# led.net
KiCad netlist of a schematic drawn in EAGLE
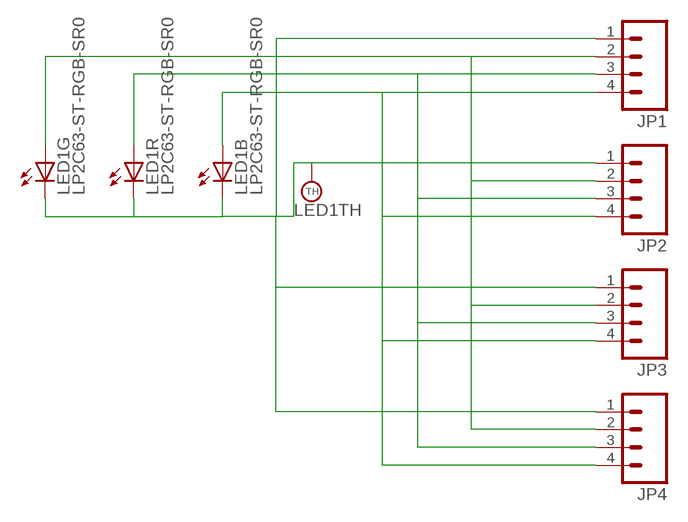
[diagram p0: schematic, sheet 1]

(export (version "E")
  (design (tool "Eeschema 10.0.6"))
  (components
    (comp (ref "JP1")
      (value "M04LONGPADS")
      (footprint "eagle-import:1X04_LONGPADS")
      (libsource (lib "eagle-import") (part "M04LONGPADS"))
    )
    (comp (ref "JP2")
      (value "M04LONGPADS")
      (footprint "eagle-import:1X04_LONGPADS")
      (libsource (lib "eagle-import") (part "M04LONGPADS"))
    )
    (comp (ref "JP3")
      (value "M04LONGPADS")
      (footprint "eagle-import:1X04_LONGPADS")
      (libsource (lib "eagle-import") (part "M04LONGPADS"))
    )
    (comp (ref "JP4")
      (value "M04LONGPADS")
      (footprint "eagle-import:1X04_LONGPADS")
      (libsource (lib "eagle-import") (part "M04LONGPADS"))
    )
    (comp (ref "LED1")
      (value "LP2C63-ST-RGB-SR0")
      (footprint "eagle-import:LP2C63-ST-RGB-SR0")
      (libsource (lib "eagle-import") (part "LP2C63-ST-RGB-SR0"))
    )
  )
  (nets
    (net (code "1") (name "Net-(LED1A-A)") (class "Default")
      (node (ref "JP1") (pin "4") (pinfunction "4_4") (pintype "passive"))
      (node (ref "JP2") (pin "4") (pinfunction "4_4") (pintype "passive"))
      (node (ref "JP3") (pin "4") (pinfunction "4_4") (pintype "passive"))
      (node (ref "JP4") (pin "4") (pinfunction "4_4") (pintype "passive"))
      (node (ref "LED1") (pin "3") (pinfunction "A_3") (pintype "passive"))
    )
    (net (code "2") (name "Net-(LED1A-C)") (class "Default")
      (node (ref "JP1") (pin "1") (pinfunction "1_1") (pintype "passive"))
      (node (ref "JP2") (pin "1") (pinfunction "1_1") (pintype "passive"))
      (node (ref "JP3") (pin "1") (pinfunction "1_1") (pintype "passive"))
      (node (ref "JP4") (pin "1") (pinfunction "1_1") (pintype "passive"))
      (node (ref "LED1") (pin "4") (pinfunction "C_4") (pintype "passive"))
      (node (ref "LED1") (pin "5") (pinfunction "C_5") (pintype "passive"))
      (node (ref "LED1") (pin "6") (pinfunction "C_6") (pintype "passive"))
    )
    (net (code "3") (name "Net-(LED1B-A)") (class "Default")
      (node (ref "JP1") (pin "2") (pinfunction "2_2") (pintype "passive"))
      (node (ref "JP2") (pin "2") (pinfunction "2_2") (pintype "passive"))
      (node (ref "JP3") (pin "2") (pinfunction "2_2") (pintype "passive"))
      (node (ref "JP4") (pin "2") (pinfunction "2_2") (pintype "passive"))
      (node (ref "LED1") (pin "1") (pinfunction "A_1") (pintype "passive"))
    )
    (net (code "4") (name "Net-(LED1C-A)") (class "Default")
      (node (ref "JP1") (pin "3") (pinfunction "3_3") (pintype "passive"))
      (node (ref "JP2") (pin "3") (pinfunction "3_3") (pintype "passive"))
      (node (ref "JP3") (pin "3") (pinfunction "3_3") (pintype "passive"))
      (node (ref "JP4") (pin "3") (pinfunction "3_3") (pintype "passive"))
      (node (ref "LED1") (pin "2") (pinfunction "A_2") (pintype "passive"))
    )
    (net (code "5") (name "unconnected-(LED1-PadTH)") (class "Default")
      (node (ref "LED1") (pin "TH") (pinfunction "TH_TH") (pintype "passive"))
    )
  )
)
